# rfid_ctl2.net
KiCad netlist of a schematic drawn in EAGLE
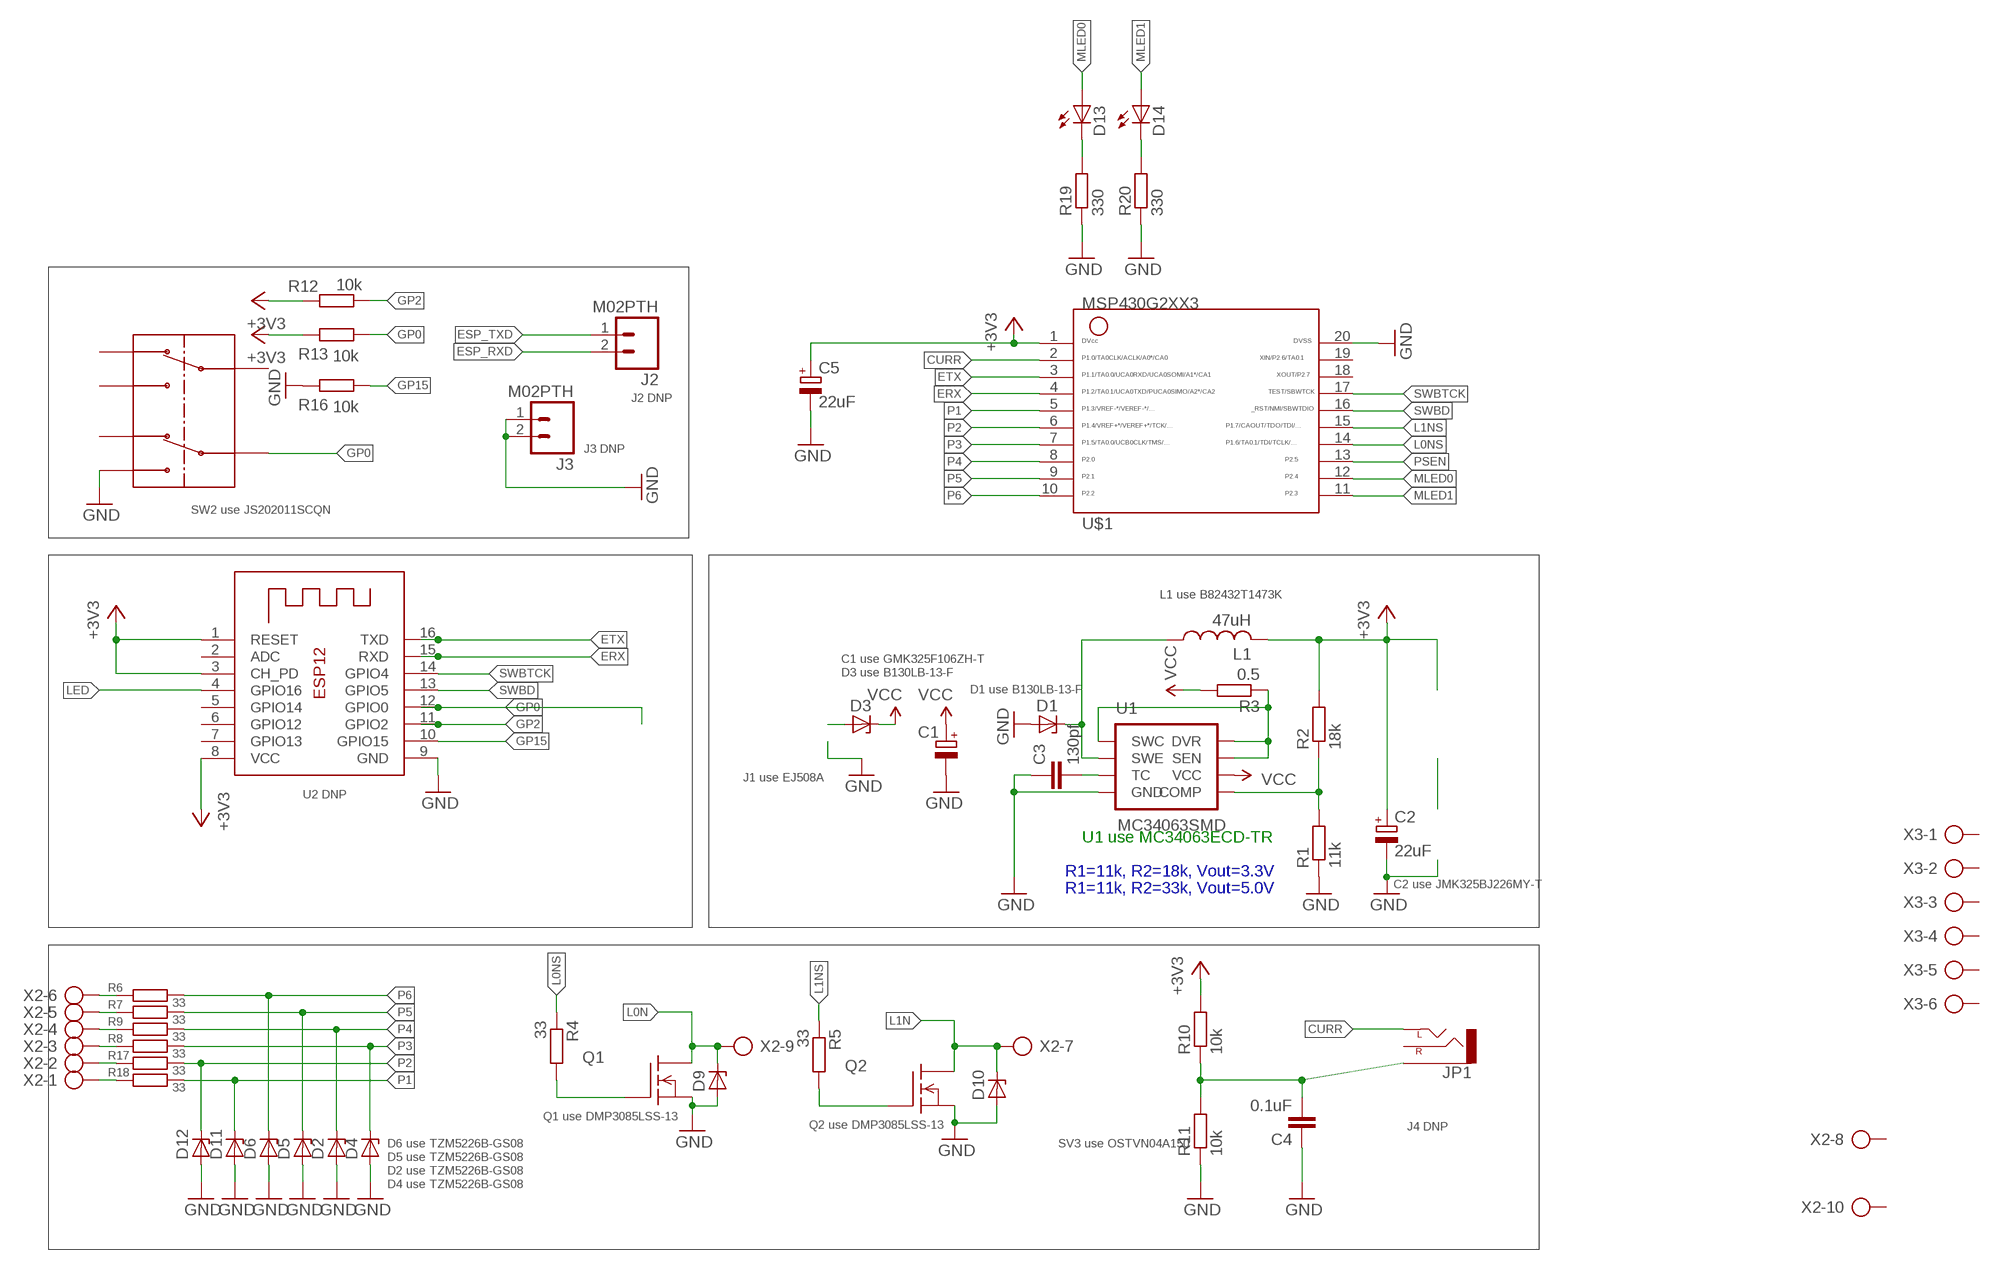
[diagram p0: schematic, sheet 1]

(export (version "E")
  (design (tool "Eeschema 10.0.6"))
  (components
    (comp (ref "C1")
      (value "CPOL-EUE2.5-7")
      (footprint "eagle-import:E2,5-7")
      (libsource (lib "eagle-import") (part "CPOL-EUE2.5-7"))
    )
    (comp (ref "C2")
      (value "22uF")
      (footprint "eagle-import:E2,5-7")
      (libsource (lib "eagle-import") (part "CPOL-EUE2.5-7"))
    )
    (comp (ref "C3")
      (value "130pf")
      (footprint "eagle-import:C0805")
      (libsource (lib "eagle-import") (part "C-EUC0805"))
    )
    (comp (ref "C4")
      (value "0.1uF")
      (footprint "eagle-import:C0603")
      (libsource (lib "eagle-import") (part "C-EUC0603"))
    )
    (comp (ref "C5")
      (value "22uF")
      (footprint "eagle-import:E1,8-4")
      (libsource (lib "eagle-import") (part "CPOL-EUE1.8-4"))
    )
    (comp (ref "D1")
      (value "ZENER-DIODESMB")
      (footprint "eagle-import:SMB")
      (libsource (lib "eagle-import") (part "ZENER-DIODESMB"))
    )
    (comp (ref "D2")
      (value "ZENER-DIODESOD80C")
      (footprint "eagle-import:SOD80C")
      (libsource (lib "eagle-import") (part "ZENER-DIODESOD80C"))
    )
    (comp (ref "D3")
      (value "ZENER-DIODESMB")
      (footprint "eagle-import:SMB")
      (libsource (lib "eagle-import") (part "ZENER-DIODESMB"))
    )
    (comp (ref "D4")
      (value "ZENER-DIODESOD80C")
      (footprint "eagle-import:SOD80C")
      (libsource (lib "eagle-import") (part "ZENER-DIODESOD80C"))
    )
    (comp (ref "D5")
      (value "ZENER-DIODESOD80C")
      (footprint "eagle-import:SOD80C")
      (libsource (lib "eagle-import") (part "ZENER-DIODESOD80C"))
    )
    (comp (ref "D6")
      (value "ZENER-DIODESOD80C")
      (footprint "eagle-import:SOD80C")
      (libsource (lib "eagle-import") (part "ZENER-DIODESOD80C"))
    )
    (comp (ref "D9")
      (value "ZENER-DIODESMB")
      (footprint "eagle-import:SMB")
      (libsource (lib "eagle-import") (part "ZENER-DIODESMB"))
    )
    (comp (ref "D10")
      (value "ZENER-DIODESMB")
      (footprint "eagle-import:SMB")
      (libsource (lib "eagle-import") (part "ZENER-DIODESMB"))
    )
    (comp (ref "D11")
      (value "ZENER-DIODESOD80C")
      (footprint "eagle-import:SOD80C")
      (libsource (lib "eagle-import") (part "ZENER-DIODESOD80C"))
    )
    (comp (ref "D12")
      (value "ZENER-DIODESOD80C")
      (footprint "eagle-import:SOD80C")
      (libsource (lib "eagle-import") (part "ZENER-DIODESOD80C"))
    )
    (comp (ref "D13")
      (value "LED5MM")
      (footprint "eagle-import:LED5MM")
      (libsource (lib "eagle-import") (part "LED5MM"))
    )
    (comp (ref "D14")
      (value "LED5MM")
      (footprint "eagle-import:LED5MM")
      (libsource (lib "eagle-import") (part "LED5MM"))
    )
    (comp (ref "J2")
      (value "M02PTH")
      (footprint "eagle-import:1X02")
      (libsource (lib "eagle-import") (part "M02PTH"))
    )
    (comp (ref "J3")
      (value "M02PTH")
      (footprint "eagle-import:1X02")
      (libsource (lib "eagle-import") (part "M02PTH"))
    )
    (comp (ref "JP1")
      (value "AUDIO-JACKSMD2")
      (footprint "eagle-import:AUDIO-JACK-3.5MM-SMD")
      (libsource (lib "eagle-import") (part "AUDIO-JACKSMD2"))
    )
    (comp (ref "L1")
      (value "47uH")
      (footprint "eagle-import:L1812")
      (libsource (lib "eagle-import") (part "L-USL1812"))
    )
    (comp (ref "Q1")
      (value "FDS5680")
      (footprint "eagle-import:SO-8")
      (libsource (lib "eagle-import") (part "FDS5680"))
    )
    (comp (ref "Q2")
      (value "FDS5680")
      (footprint "eagle-import:SO-8")
      (libsource (lib "eagle-import") (part "FDS5680"))
    )
    (comp (ref "R1")
      (value "11k")
      (footprint "eagle-import:R0805")
      (libsource (lib "eagle-import") (part "R-EU_R0805"))
    )
    (comp (ref "R2")
      (value "18k")
      (footprint "eagle-import:R0805")
      (libsource (lib "eagle-import") (part "R-EU_R0805"))
    )
    (comp (ref "R3")
      (value "0.5")
      (footprint "eagle-import:R0805")
      (libsource (lib "eagle-import") (part "R-EU_R0805"))
    )
    (comp (ref "R4")
      (value "33")
      (footprint "eagle-import:R0805")
      (libsource (lib "eagle-import") (part "R-EU_R0805"))
    )
    (comp (ref "R5")
      (value "33")
      (footprint "eagle-import:R0805")
      (libsource (lib "eagle-import") (part "R-EU_R0805"))
    )
    (comp (ref "R6")
      (value "33")
      (footprint "eagle-import:R1206")
      (libsource (lib "eagle-import") (part "R-EU_R1206"))
    )
    (comp (ref "R7")
      (value "33")
      (footprint "eagle-import:R1206")
      (libsource (lib "eagle-import") (part "R-EU_R1206"))
    )
    (comp (ref "R8")
      (value "33")
      (footprint "eagle-import:R1206")
      (libsource (lib "eagle-import") (part "R-EU_R1206"))
    )
    (comp (ref "R9")
      (value "33")
      (footprint "eagle-import:R1206")
      (libsource (lib "eagle-import") (part "R-EU_R1206"))
    )
    (comp (ref "R10")
      (value "10k")
      (footprint "eagle-import:R0603")
      (libsource (lib "eagle-import") (part "R-EU_R0603"))
    )
    (comp (ref "R11")
      (value "10k")
      (footprint "eagle-import:R0603")
      (libsource (lib "eagle-import") (part "R-EU_R0603"))
    )
    (comp (ref "R12")
      (value "10k")
      (footprint "eagle-import:R0805")
      (libsource (lib "eagle-import") (part "R-EU_R0805"))
    )
    (comp (ref "R13")
      (value "10k")
      (footprint "eagle-import:R0805")
      (libsource (lib "eagle-import") (part "R-EU_R0805"))
    )
    (comp (ref "R16")
      (value "10k")
      (footprint "eagle-import:R0603")
      (libsource (lib "eagle-import") (part "R-EU_R0603"))
    )
    (comp (ref "R17")
      (value "33")
      (footprint "eagle-import:R1206")
      (libsource (lib "eagle-import") (part "R-EU_R1206"))
    )
    (comp (ref "R18")
      (value "33")
      (footprint "eagle-import:R1206")
      (libsource (lib "eagle-import") (part "R-EU_R1206"))
    )
    (comp (ref "R19")
      (value "330")
      (footprint "eagle-import:R0805")
      (libsource (lib "eagle-import") (part "R-EU_R0805"))
    )
    (comp (ref "R20")
      (value "330")
      (footprint "eagle-import:R0805")
      (libsource (lib "eagle-import") (part "R-EU_R0805"))
    )
    (comp (ref "SW2")
      (value "L202011MS02Q")
      (footprint "eagle-import:SMT")
      (libsource (lib "eagle-import") (part "L202011MS02Q"))
    )
    (comp (ref "U$1")
      (value "G2XX3---N20")
      (footprint "eagle-import:N20")
      (libsource (lib "eagle-import") (part "G2XX3---N20"))
    )
    (comp (ref "U1")
      (value "MC34063SMD")
      (footprint "eagle-import:SO08")
      (libsource (lib "eagle-import") (part "MC34063SMD"))
    )
    (comp (ref "U2")
      (value "ESP-12")
      (footprint "eagle-import:ESP-12")
      (libsource (lib "eagle-import") (part "ESP-12"))
    )
    (comp (ref "X2")
      (value "AK300/10")
      (footprint "eagle-import:AK300_10")
      (libsource (lib "eagle-import") (part "AK300/10"))
    )
    (comp (ref "X3")
      (value "AK300/6")
      (footprint "eagle-import:AK300_6")
      (libsource (lib "eagle-import") (part "AK300/6"))
    )
  )
  (nets
    (net (code "1") (name "+3V3") (class "Default")
      (node (ref "C2") (pin "+") (pinfunction "+_+") (pintype "passive"))
      (node (ref "C5") (pin "+") (pinfunction "+_+") (pintype "passive"))
      (node (ref "L1") (pin "2") (pinfunction "2_2") (pintype "passive"))
      (node (ref "R10") (pin "2") (pinfunction "2_2") (pintype "passive"))
      (node (ref "R12") (pin "2") (pinfunction "2_2") (pintype "passive"))
      (node (ref "R13") (pin "2") (pinfunction "2_2") (pintype "passive"))
      (node (ref "R2") (pin "2") (pinfunction "2_2") (pintype "passive"))
      (node (ref "U$1") (pin "1") (pinfunction "1_1") (pintype "bidirectional"))
      (node (ref "U2") (pin "1") (pinfunction "RESET_1") (pintype "input"))
      (node (ref "U2") (pin "3") (pinfunction "CH_PD_3") (pintype "input"))
      (node (ref "U2") (pin "8") (pinfunction "VCC_8") (pintype "power_in"))
    )
    (net (code "2") (name "CURR") (class "Default")
      (node (ref "JP1") (pin "TIP") (pinfunction "LEFT_TIP") (pintype "bidirectional"))
      (node (ref "U$1") (pin "2") (pinfunction "2_2") (pintype "bidirectional"))
    )
    (net (code "3") (name "ERX") (class "Default")
      (node (ref "U$1") (pin "4") (pinfunction "4_4") (pintype "bidirectional"))
      (node (ref "U2") (pin "15") (pinfunction "RXD_15") (pintype "input"))
    )
    (net (code "4") (name "ESP_RXD") (class "Default")
      (node (ref "J2") (pin "2") (pinfunction "2_2") (pintype "passive"))
    )
    (net (code "5") (name "ESP_TXD") (class "Default")
      (node (ref "J2") (pin "1") (pinfunction "1_1") (pintype "passive"))
    )
    (net (code "6") (name "ETX") (class "Default")
      (node (ref "U$1") (pin "3") (pinfunction "3_3") (pintype "bidirectional"))
      (node (ref "U2") (pin "16") (pinfunction "TXD_16") (pintype "output"))
    )
    (net (code "7") (name "GND") (class "Default")
      (node (ref "C1") (pin "-") (pinfunction "-_-") (pintype "passive"))
      (node (ref "C2") (pin "-") (pinfunction "-_-") (pintype "passive"))
      (node (ref "C3") (pin "1") (pinfunction "1_1") (pintype "passive"))
      (node (ref "C4") (pin "1") (pinfunction "1_1") (pintype "passive"))
      (node (ref "C5") (pin "-") (pinfunction "-_-") (pintype "passive"))
      (node (ref "D1") (pin "A") (pinfunction "A_A") (pintype "passive"))
      (node (ref "D10") (pin "A") (pinfunction "A_A") (pintype "passive"))
      (node (ref "D11") (pin "A") (pinfunction "A_A") (pintype "passive"))
      (node (ref "D12") (pin "A") (pinfunction "A_A") (pintype "passive"))
      (node (ref "D2") (pin "A") (pinfunction "A_A") (pintype "passive"))
      (node (ref "D4") (pin "A") (pinfunction "A_A") (pintype "passive"))
      (node (ref "D5") (pin "A") (pinfunction "A_A") (pintype "passive"))
      (node (ref "D6") (pin "A") (pinfunction "A_A") (pintype "passive"))
      (node (ref "D9") (pin "A") (pinfunction "A_A") (pintype "passive"))
      (node (ref "J3") (pin "1") (pinfunction "1_1") (pintype "passive"))
      (node (ref "J3") (pin "2") (pinfunction "2_2") (pintype "passive"))
      (node (ref "Q1") (pin "1") (pinfunction "S_1") (pintype "passive"))
      (node (ref "Q1") (pin "2") (pinfunction "S_2") (pintype "passive"))
      (node (ref "Q1") (pin "3") (pinfunction "S_3") (pintype "passive"))
      (node (ref "Q2") (pin "1") (pinfunction "S_1") (pintype "passive"))
      (node (ref "Q2") (pin "2") (pinfunction "S_2") (pintype "passive"))
      (node (ref "Q2") (pin "3") (pinfunction "S_3") (pintype "passive"))
      (node (ref "R1") (pin "1") (pinfunction "1_1") (pintype "passive"))
      (node (ref "R11") (pin "1") (pinfunction "1_1") (pintype "passive"))
      (node (ref "R16") (pin "2") (pinfunction "2_2") (pintype "passive"))
      (node (ref "R19") (pin "1") (pinfunction "1_1") (pintype "passive"))
      (node (ref "R20") (pin "1") (pinfunction "1_1") (pintype "passive"))
      (node (ref "SW2") (pin "B1") (pinfunction "B1_B1") (pintype "bidirectional"))
      (node (ref "U$1") (pin "20") (pinfunction "20_20") (pintype "bidirectional"))
      (node (ref "U1") (pin "4") (pinfunction "GND_4") (pintype "bidirectional"))
      (node (ref "U2") (pin "9") (pinfunction "GND_9") (pintype "power_in"))
    )
    (net (code "8") (name "GP0") (class "Default")
      (node (ref "R13") (pin "1") (pinfunction "1_1") (pintype "passive"))
      (node (ref "SW2") (pin "B") (pinfunction "B_B") (pintype "bidirectional"))
      (node (ref "U2") (pin "12") (pinfunction "GPIO0_12") (pintype "bidirectional"))
    )
    (net (code "9") (name "GP2") (class "Default")
      (node (ref "R12") (pin "1") (pinfunction "1_1") (pintype "passive"))
      (node (ref "U2") (pin "11") (pinfunction "GPIO2_11") (pintype "bidirectional"))
    )
    (net (code "10") (name "GP15") (class "Default")
      (node (ref "R16") (pin "1") (pinfunction "1_1") (pintype "passive"))
      (node (ref "U2") (pin "10") (pinfunction "GPIO15_10") (pintype "bidirectional"))
    )
    (net (code "11") (name "L0N") (class "Default")
      (node (ref "D9") (pin "C") (pinfunction "C_C") (pintype "passive"))
      (node (ref "Q1") (pin "5") (pinfunction "D_5") (pintype "passive"))
      (node (ref "Q1") (pin "6") (pinfunction "D_6") (pintype "passive"))
      (node (ref "Q1") (pin "7") (pinfunction "D_7") (pintype "passive"))
      (node (ref "Q1") (pin "8") (pinfunction "D_8") (pintype "passive"))
      (node (ref "X2") (pin "9") (pinfunction "KL_9") (pintype "passive"))
    )
    (net (code "12") (name "L0NS") (class "Default")
      (node (ref "R4") (pin "1") (pinfunction "1_1") (pintype "passive"))
      (node (ref "U$1") (pin "14") (pinfunction "14_14") (pintype "bidirectional"))
    )
    (net (code "13") (name "L1N") (class "Default")
      (node (ref "D10") (pin "C") (pinfunction "C_C") (pintype "passive"))
      (node (ref "Q2") (pin "5") (pinfunction "D_5") (pintype "passive"))
      (node (ref "Q2") (pin "6") (pinfunction "D_6") (pintype "passive"))
      (node (ref "Q2") (pin "7") (pinfunction "D_7") (pintype "passive"))
      (node (ref "Q2") (pin "8") (pinfunction "D_8") (pintype "passive"))
      (node (ref "X2") (pin "7") (pinfunction "KL_7") (pintype "passive"))
    )
    (net (code "14") (name "L1NS") (class "Default")
      (node (ref "R5") (pin "1") (pinfunction "1_1") (pintype "passive"))
      (node (ref "U$1") (pin "15") (pinfunction "15_15") (pintype "bidirectional"))
    )
    (net (code "15") (name "LED") (class "Default")
      (node (ref "U2") (pin "4") (pinfunction "GPIO16_4") (pintype "bidirectional"))
    )
    (net (code "16") (name "MLED0") (class "Default")
      (node (ref "D13") (pin "A") (pinfunction "A_A") (pintype "passive"))
      (node (ref "U$1") (pin "12") (pinfunction "12_12") (pintype "bidirectional"))
    )
    (net (code "17") (name "MLED1") (class "Default")
      (node (ref "D14") (pin "A") (pinfunction "A_A") (pintype "passive"))
      (node (ref "U$1") (pin "11") (pinfunction "11_11") (pintype "bidirectional"))
    )
    (net (code "18") (name "Net-(C4-Pad2)") (class "Default")
      (node (ref "C4") (pin "2") (pinfunction "2_2") (pintype "passive"))
      (node (ref "JP1") (pin "SLEEVE") (pinfunction "SLEEVE_SLEEVE") (pintype "bidirectional"))
      (node (ref "R10") (pin "1") (pinfunction "1_1") (pintype "passive"))
      (node (ref "R11") (pin "2") (pinfunction "2_2") (pintype "passive"))
    )
    (net (code "19") (name "Net-(D13-C)") (class "Default")
      (node (ref "D13") (pin "K") (pinfunction "C_K") (pintype "passive"))
      (node (ref "R19") (pin "2") (pinfunction "2_2") (pintype "passive"))
    )
    (net (code "20") (name "Net-(D14-C)") (class "Default")
      (node (ref "D14") (pin "K") (pinfunction "C_K") (pintype "passive"))
      (node (ref "R20") (pin "2") (pinfunction "2_2") (pintype "passive"))
    )
    (net (code "21") (name "Net-(Q1-G)") (class "Default")
      (node (ref "Q1") (pin "4") (pinfunction "G_4") (pintype "passive"))
      (node (ref "R4") (pin "2") (pinfunction "2_2") (pintype "passive"))
    )
    (net (code "22") (name "Net-(Q2-G)") (class "Default")
      (node (ref "Q2") (pin "4") (pinfunction "G_4") (pintype "passive"))
      (node (ref "R5") (pin "2") (pinfunction "2_2") (pintype "passive"))
    )
    (net (code "23") (name "Net-(U1-COMP)") (class "Default")
      (node (ref "R1") (pin "2") (pinfunction "2_2") (pintype "passive"))
      (node (ref "R2") (pin "1") (pinfunction "1_1") (pintype "passive"))
      (node (ref "U1") (pin "5") (pinfunction "COMP_5") (pintype "bidirectional"))
    )
    (net (code "24") (name "Net-(U1-DVR)") (class "Default")
      (node (ref "R3") (pin "1") (pinfunction "1_1") (pintype "passive"))
      (node (ref "U1") (pin "1") (pinfunction "SWC_1") (pintype "bidirectional"))
      (node (ref "U1") (pin "7") (pinfunction "SEN_7") (pintype "bidirectional"))
      (node (ref "U1") (pin "8") (pinfunction "DVR_8") (pintype "bidirectional"))
    )
    (net (code "25") (name "Net-(U1-SWE)") (class "Default")
      (node (ref "D1") (pin "C") (pinfunction "C_C") (pintype "passive"))
      (node (ref "L1") (pin "1") (pinfunction "1_1") (pintype "passive"))
      (node (ref "U1") (pin "2") (pinfunction "SWE_2") (pintype "bidirectional"))
    )
    (net (code "26") (name "Net-(U1-TC)") (class "Default")
      (node (ref "C3") (pin "2") (pinfunction "2_2") (pintype "passive"))
      (node (ref "U1") (pin "3") (pinfunction "TC_3") (pintype "bidirectional"))
    )
    (net (code "27") (name "Net-(X2A-KL)") (class "Default")
      (node (ref "R18") (pin "1") (pinfunction "1_1") (pintype "passive"))
      (node (ref "X2") (pin "1") (pinfunction "KL_1") (pintype "passive"))
    )
    (net (code "28") (name "Net-(X2C-KL)") (class "Default")
      (node (ref "R17") (pin "1") (pinfunction "1_1") (pintype "passive"))
      (node (ref "X2") (pin "2") (pinfunction "KL_2") (pintype "passive"))
    )
    (net (code "29") (name "Net-(X2D-KL)") (class "Default")
      (node (ref "R9") (pin "1") (pinfunction "1_1") (pintype "passive"))
      (node (ref "X2") (pin "3") (pinfunction "KL_3") (pintype "passive"))
    )
    (net (code "30") (name "Net-(X2E-KL)") (class "Default")
      (node (ref "R8") (pin "1") (pinfunction "1_1") (pintype "passive"))
      (node (ref "X2") (pin "4") (pinfunction "KL_4") (pintype "passive"))
    )
    (net (code "31") (name "Net-(X2F-KL)") (class "Default")
      (node (ref "R7") (pin "1") (pinfunction "1_1") (pintype "passive"))
      (node (ref "X2") (pin "5") (pinfunction "KL_5") (pintype "passive"))
    )
    (net (code "32") (name "Net-(X2G-KL)") (class "Default")
      (node (ref "R6") (pin "1") (pinfunction "1_1") (pintype "passive"))
      (node (ref "X2") (pin "6") (pinfunction "KL_6") (pintype "passive"))
    )
    (net (code "33") (name "P1") (class "Default")
      (node (ref "D11") (pin "C") (pinfunction "C_C") (pintype "passive"))
      (node (ref "R18") (pin "2") (pinfunction "2_2") (pintype "passive"))
      (node (ref "U$1") (pin "5") (pinfunction "5_5") (pintype "bidirectional"))
    )
    (net (code "34") (name "P2") (class "Default")
      (node (ref "D12") (pin "C") (pinfunction "C_C") (pintype "passive"))
      (node (ref "R17") (pin "2") (pinfunction "2_2") (pintype "passive"))
      (node (ref "U$1") (pin "6") (pinfunction "6_6") (pintype "bidirectional"))
    )
    (net (code "35") (name "P3") (class "Default")
      (node (ref "D4") (pin "C") (pinfunction "C_C") (pintype "passive"))
      (node (ref "R9") (pin "2") (pinfunction "2_2") (pintype "passive"))
      (node (ref "U$1") (pin "7") (pinfunction "7_7") (pintype "bidirectional"))
    )
    (net (code "36") (name "P4") (class "Default")
      (node (ref "D2") (pin "C") (pinfunction "C_C") (pintype "passive"))
      (node (ref "R8") (pin "2") (pinfunction "2_2") (pintype "passive"))
      (node (ref "U$1") (pin "8") (pinfunction "8_8") (pintype "bidirectional"))
    )
    (net (code "37") (name "P5") (class "Default")
      (node (ref "D5") (pin "C") (pinfunction "C_C") (pintype "passive"))
      (node (ref "R7") (pin "2") (pinfunction "2_2") (pintype "passive"))
      (node (ref "U$1") (pin "9") (pinfunction "9_9") (pintype "bidirectional"))
    )
    (net (code "38") (name "P6") (class "Default")
      (node (ref "D6") (pin "C") (pinfunction "C_C") (pintype "passive"))
      (node (ref "R6") (pin "2") (pinfunction "2_2") (pintype "passive"))
      (node (ref "U$1") (pin "10") (pinfunction "10_10") (pintype "bidirectional"))
    )
    (net (code "39") (name "PSEN") (class "Default")
      (node (ref "U$1") (pin "13") (pinfunction "13_13") (pintype "bidirectional"))
    )
    (net (code "40") (name "SWBD") (class "Default")
      (node (ref "U$1") (pin "16") (pinfunction "16_16") (pintype "bidirectional"))
      (node (ref "U2") (pin "13") (pinfunction "GPIO5_13") (pintype "bidirectional"))
    )
    (net (code "41") (name "SWBTCK") (class "Default")
      (node (ref "U$1") (pin "17") (pinfunction "17_17") (pintype "bidirectional"))
      (node (ref "U2") (pin "14") (pinfunction "GPIO4_14") (pintype "bidirectional"))
    )
    (net (code "42") (name "VCC") (class "Default")
      (node (ref "C1") (pin "+") (pinfunction "+_+") (pintype "passive"))
      (node (ref "D3") (pin "C") (pinfunction "C_C") (pintype "passive"))
      (node (ref "R3") (pin "2") (pinfunction "2_2") (pintype "passive"))
      (node (ref "U1") (pin "6") (pinfunction "VCC_6") (pintype "bidirectional"))
    )
    (net (code "43") (name "unconnected-(D3-PadA)") (class "Default")
      (node (ref "D3") (pin "A") (pinfunction "A_A") (pintype "passive"))
    )
    (net (code "44") (name "unconnected-(JP1-RIGHT-PadRING)") (class "Default")
      (node (ref "JP1") (pin "RING") (pinfunction "RIGHT_RING") (pintype "bidirectional"))
    )
    (net (code "45") (name "unconnected-(SW2-PadA)") (class "Default")
      (node (ref "SW2") (pin "A") (pinfunction "A_A") (pintype "bidirectional"))
    )
    (net (code "46") (name "unconnected-(SW2-PadA1)") (class "Default")
      (node (ref "SW2") (pin "A1") (pinfunction "A1_A1") (pintype "bidirectional"))
    )
    (net (code "47") (name "unconnected-(SW2-PadA2)") (class "Default")
      (node (ref "SW2") (pin "A2") (pinfunction "A2_A2") (pintype "bidirectional"))
    )
    (net (code "48") (name "unconnected-(SW2-PadB2)") (class "Default")
      (node (ref "SW2") (pin "B2") (pinfunction "B2_B2") (pintype "bidirectional"))
    )
    (net (code "49") (name "unconnected-(U$1-Pad18)") (class "Default")
      (node (ref "U$1") (pin "18") (pinfunction "18_18") (pintype "bidirectional"))
    )
    (net (code "50") (name "unconnected-(U$1-Pad19)") (class "Default")
      (node (ref "U$1") (pin "19") (pinfunction "19_19") (pintype "bidirectional"))
    )
    (net (code "51") (name "unconnected-(U2-ADC-Pad2)") (class "Default")
      (node (ref "U2") (pin "2") (pinfunction "ADC_2") (pintype "passive"))
    )
    (net (code "52") (name "unconnected-(U2-GPIO12-Pad6)") (class "Default")
      (node (ref "U2") (pin "6") (pinfunction "GPIO12_6") (pintype "bidirectional"))
    )
    (net (code "53") (name "unconnected-(U2-GPIO13-Pad7)") (class "Default")
      (node (ref "U2") (pin "7") (pinfunction "GPIO13_7") (pintype "bidirectional"))
    )
    (net (code "54") (name "unconnected-(U2-GPIO14-Pad5)") (class "Default")
      (node (ref "U2") (pin "5") (pinfunction "GPIO14_5") (pintype "bidirectional"))
    )
    (net (code "55") (name "unconnected-(X2B-KL-Pad10)") (class "Default")
      (node (ref "X2") (pin "10") (pinfunction "KL_10") (pintype "passive"))
    )
    (net (code "56") (name "unconnected-(X2I-KL-Pad8)") (class "Default")
      (node (ref "X2") (pin "8") (pinfunction "KL_8") (pintype "passive"))
    )
    (net (code "57") (name "unconnected-(X3A-KL-Pad1)") (class "Default")
      (node (ref "X3") (pin "1") (pinfunction "KL_1") (pintype "passive"))
    )
    (net (code "58") (name "unconnected-(X3B-KL-Pad2)") (class "Default")
      (node (ref "X3") (pin "2") (pinfunction "KL_2") (pintype "passive"))
    )
    (net (code "59") (name "unconnected-(X3C-KL-Pad3)") (class "Default")
      (node (ref "X3") (pin "3") (pinfunction "KL_3") (pintype "passive"))
    )
    (net (code "60") (name "unconnected-(X3D-KL-Pad4)") (class "Default")
      (node (ref "X3") (pin "4") (pinfunction "KL_4") (pintype "passive"))
    )
    (net (code "61") (name "unconnected-(X3E-KL-Pad5)") (class "Default")
      (node (ref "X3") (pin "5") (pinfunction "KL_5") (pintype "passive"))
    )
    (net (code "62") (name "unconnected-(X3F-KL-Pad6)") (class "Default")
      (node (ref "X3") (pin "6") (pinfunction "KL_6") (pintype "passive"))
    )
  )
)
